# Peripherals.net
KiCad netlist of a schematic drawn in Altium Designer
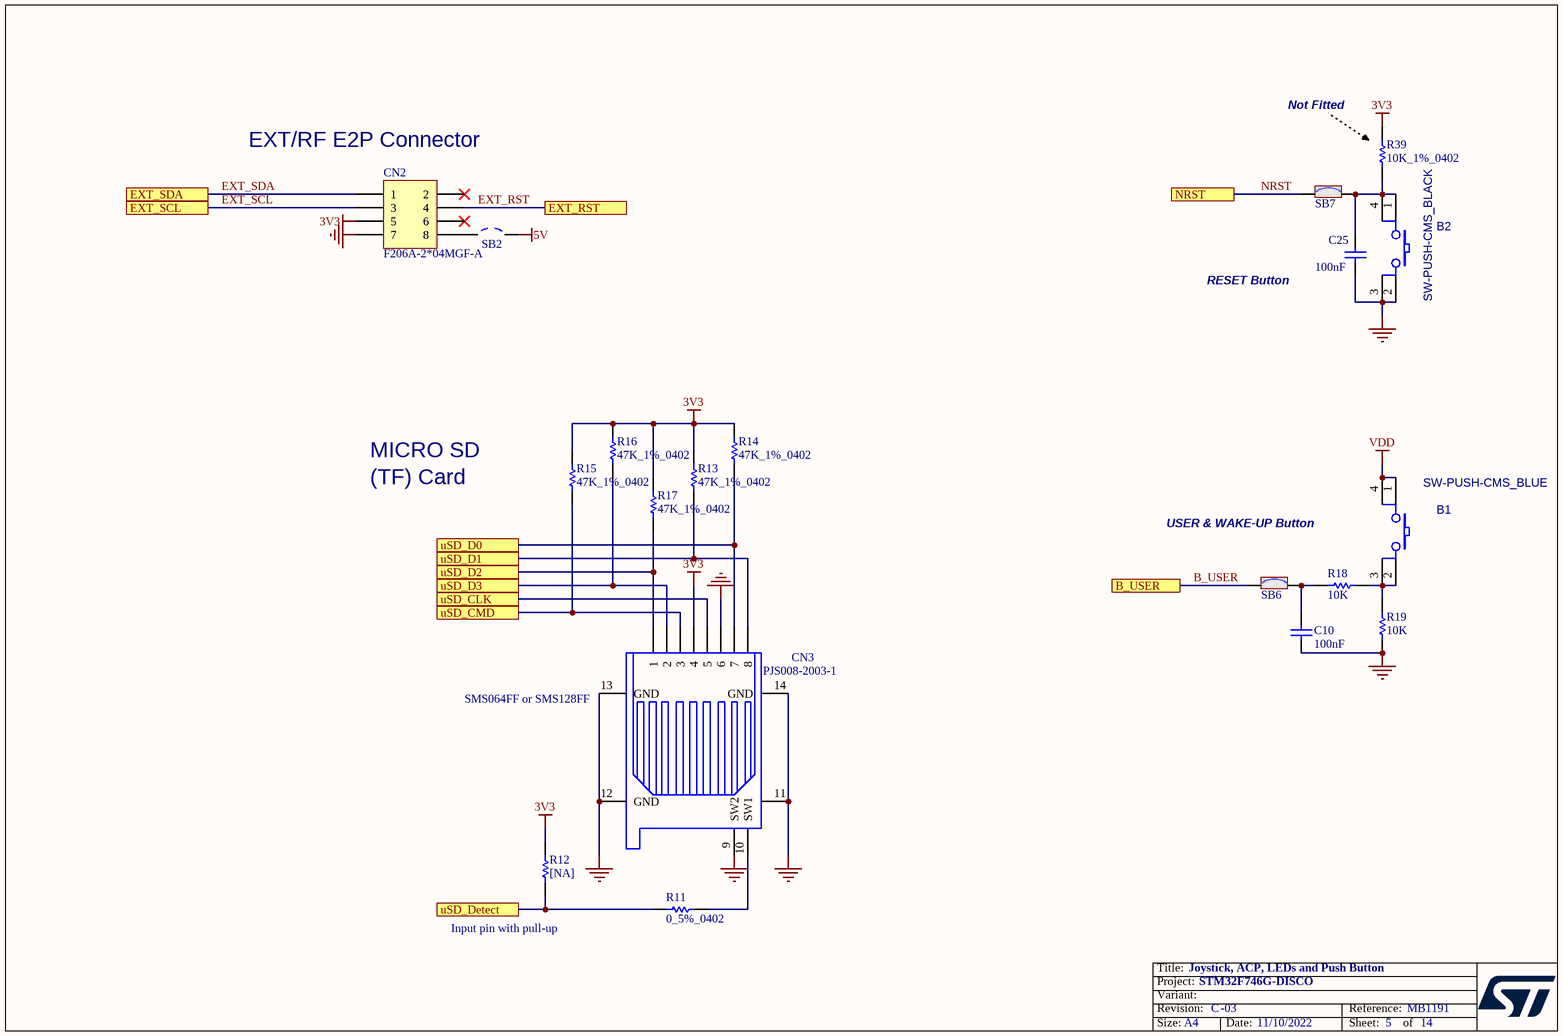
[diagram p0: Peripherals.SchDoc]

(export (version "E")
  (design (tool "Eeschema 10.0.6"))
  (components
    (comp (ref "B1")
      (value "SW-PUSH-CMS_BLUE")
      (footprint "BP1CMS")
      (description "Non-Open Push-Button 0.1A 24V")
      (libsource (lib "MCD_TOOLS") (part "SW-PUSH-CMS_BLUE"))
    )
    (comp (ref "B2")
      (value "SW-PUSH-CMS_BLACK")
      (footprint "BP1CMS")
      (description "Non-Open Push-Button 0.1A 24V")
      (libsource (lib "MCD_TOOLS") (part "SW-PUSH-CMS_BLACK"))
    )
    (comp (ref "C10")
      (value "100nF")
      (footprint "0402C")
      (description "Capacitor,100nF,16V,X7R,10%,0402,YAGEO")
      (libsource (lib "MCD_TOOLS") (part "Cap_100nF_X7R_10%_0402"))
    )
    (comp (ref "C25")
      (value "100nF")
      (footprint "0402C")
      (description "Capacitor,100nF,16V,X7R,10%,0402,YAGEO")
      (libsource (lib "MCD_TOOLS") (part "Cap_100nF_X7R_10%_0402"))
    )
    (comp (ref "CN2")
      (value "F206A-2*04MGF-A")
      (footprint "SSM-104-L-DH")
      (description "Header, 5-Pins, Horizontal Dual row, female SMD")
      (libsource (lib "MCD_TOOLS") (part "F206A-2*04MGF-A"))
    )
    (comp (ref "CN3")
      (value "PJS008-2003-1")
      (footprint "PJS008-2003-1")
      (description "Memory Card Connectors MicroSD Card Conn Revrs Mnt Push-Push")
      (libsource (lib "Mb1191") (part "microSD-PJS008-2003"))
    )
    (comp (ref "R11")
      (value "0_5%_0402")
      (footprint "0402R")
      (description "Resistor,0,0402,5%,YAGEO")
      (libsource (lib "MCD_TOOLS") (part "Res_0_5%_0402"))
    )
    (comp (ref "R12")
      (value "[NA]")
      (footprint "0402R")
      (description "Resistor,[NA],0402")
      (libsource (lib "MCD_TOOLS") (part "Res_NA_0402"))
    )
    (comp (ref "R13")
      (value "47K_1%_0402")
      (footprint "0402R")
      (description "Resistor,47K,0402,1%,YAGEO")
      (libsource (lib "MCD_TOOLS") (part "Res_47K_1%_0402"))
    )
    (comp (ref "R14")
      (value "47K_1%_0402")
      (footprint "0402R")
      (description "Resistor,47K,0402,1%,YAGEO")
      (libsource (lib "MCD_TOOLS") (part "Res_47K_1%_0402"))
    )
    (comp (ref "R15")
      (value "47K_1%_0402")
      (footprint "0402R")
      (description "Resistor,47K,0402,1%,YAGEO")
      (libsource (lib "MCD_TOOLS") (part "Res_47K_1%_0402"))
    )
    (comp (ref "R16")
      (value "47K_1%_0402")
      (footprint "0402R")
      (description "Resistor,47K,0402,1%,YAGEO")
      (libsource (lib "MCD_TOOLS") (part "Res_47K_1%_0402"))
    )
    (comp (ref "R17")
      (value "47K_1%_0402")
      (footprint "0402R")
      (description "Resistor,47K,0402,1%,YAGEO")
      (libsource (lib "MCD_TOOLS") (part "Res_47K_1%_0402"))
    )
    (comp (ref "R18")
      (value "10K")
      (footprint "0402R")
      (description "Resistor,10K,0402,1%,YAGEO")
      (libsource (lib "MCD_TOOLS") (part "Res_10K_1%_0402"))
    )
    (comp (ref "R19")
      (value "10K")
      (footprint "0402R")
      (description "Resistor,10K,0402,1%,YAGEO")
      (libsource (lib "MCD_TOOLS") (part "Res_10K_1%_0402"))
    )
    (comp (ref "R39")
      (value "10K_1%_0402")
      (footprint "0402R")
      (description "Resistor,10K,0402,1%,YAGEO")
      (libsource (lib "MCD_TOOLS") (part "Res_10K_1%_0402"))
    )
    (comp (ref "SB2")
      (value "Solder Bridge OFF")
      (footprint "JP2_SMD")
      (libsource (lib "MCD_TOOLS") (part "SB_OFF"))
    )
    (comp (ref "SB6")
      (value "Solder Bridge ON")
      (footprint "JP2_SMD")
      (libsource (lib "MCD_TOOLS") (part "SB_ON"))
    )
    (comp (ref "SB7")
      (value "Solder Bridge ON")
      (footprint "JP2_SMD")
      (libsource (lib "MCD_TOOLS") (part "SB_ON"))
    )
  )
  (nets
    (net (code "1") (name "/B_USER") (class "Default")
      (node (ref "SB6") (pin "1") (pinfunction "1_1") (pintype "passive"))
    )
    (net (code "2") (name "/EXT_RST") (class "Default")
      (node (ref "CN2") (pin "4") (pinfunction "4_4") (pintype "passive"))
    )
    (net (code "3") (name "/EXT_SCL") (class "Default")
      (node (ref "CN2") (pin "3") (pinfunction "3_3") (pintype "passive"))
    )
    (net (code "4") (name "/EXT_SDA") (class "Default")
      (node (ref "CN2") (pin "1") (pinfunction "1_1") (pintype "passive"))
    )
    (net (code "5") (name "/NRST") (class "Default")
      (node (ref "SB7") (pin "1") (pinfunction "1_1") (pintype "passive"))
    )
    (net (code "6") (name "/uSD_CLK") (class "Default")
      (node (ref "CN3") (pin "5") (pinfunction "5_5") (pintype "passive"))
    )
    (net (code "7") (name "/uSD_CMD") (class "Default")
      (node (ref "CN3") (pin "3") (pinfunction "3_3") (pintype "passive"))
      (node (ref "R15") (pin "1") (pinfunction "1_1") (pintype "passive"))
    )
    (net (code "8") (name "/uSD_D0") (class "Default")
      (node (ref "CN3") (pin "7") (pinfunction "7_7") (pintype "passive"))
      (node (ref "R14") (pin "1") (pinfunction "1_1") (pintype "passive"))
    )
    (net (code "9") (name "/uSD_D1") (class "Default")
      (node (ref "CN3") (pin "8") (pinfunction "8_8") (pintype "passive"))
      (node (ref "R13") (pin "1") (pinfunction "1_1") (pintype "passive"))
    )
    (net (code "10") (name "/uSD_D2") (class "Default")
      (node (ref "CN3") (pin "1") (pinfunction "1_1") (pintype "passive"))
      (node (ref "R17") (pin "1") (pinfunction "1_1") (pintype "passive"))
    )
    (net (code "11") (name "/uSD_D3") (class "Default")
      (node (ref "CN3") (pin "2") (pinfunction "2_2") (pintype "passive"))
      (node (ref "R16") (pin "1") (pinfunction "1_1") (pintype "passive"))
    )
    (net (code "12") (name "/uSD_Detect") (class "Default")
      (node (ref "R11") (pin "1") (pinfunction "1_1") (pintype "passive"))
      (node (ref "R12") (pin "1") (pinfunction "1_1") (pintype "passive"))
    )
    (net (code "13") (name "3V3") (class "Default")
      (node (ref "CN2") (pin "5") (pinfunction "5_5") (pintype "passive"))
      (node (ref "CN3") (pin "4") (pinfunction "4_4") (pintype "passive"))
      (node (ref "R12") (pin "2") (pinfunction "2_2") (pintype "passive"))
      (node (ref "R13") (pin "2") (pinfunction "2_2") (pintype "passive"))
      (node (ref "R14") (pin "2") (pinfunction "2_2") (pintype "passive"))
      (node (ref "R15") (pin "2") (pinfunction "2_2") (pintype "passive"))
      (node (ref "R16") (pin "2") (pinfunction "2_2") (pintype "passive"))
      (node (ref "R17") (pin "2") (pinfunction "2_2") (pintype "passive"))
      (node (ref "R39") (pin "2") (pinfunction "2_2") (pintype "passive"))
    )
    (net (code "14") (name "5V") (class "Default")
      (node (ref "SB2") (pin "2") (pinfunction "2_2") (pintype "passive"))
    )
    (net (code "15") (name "GND") (class "Default")
      (node (ref "B2") (pin "2") (pinfunction "2_2") (pintype "passive"))
      (node (ref "B2") (pin "3") (pinfunction "3_3") (pintype "passive"))
      (node (ref "C10") (pin "1") (pinfunction "1_1") (pintype "passive"))
      (node (ref "C25") (pin "1") (pinfunction "1_1") (pintype "passive"))
      (node (ref "CN2") (pin "7") (pinfunction "7_7") (pintype "passive"))
      (node (ref "CN3") (pin "11") (pinfunction "GND_11") (pintype "passive"))
      (node (ref "CN3") (pin "12") (pinfunction "GND_12") (pintype "passive"))
      (node (ref "CN3") (pin "13") (pinfunction "GND_13") (pintype "passive"))
      (node (ref "CN3") (pin "14") (pinfunction "GND_14") (pintype "passive"))
      (node (ref "CN3") (pin "6") (pinfunction "6_6") (pintype "passive"))
      (node (ref "CN3") (pin "9") (pinfunction "SW2_9") (pintype "passive"))
      (node (ref "R19") (pin "1") (pinfunction "1_1") (pintype "passive"))
    )
    (net (code "16") (name "Net-(B1-Pad2)") (class "Default")
      (node (ref "B1") (pin "2") (pinfunction "2_2") (pintype "passive"))
      (node (ref "B1") (pin "3") (pinfunction "3_3") (pintype "passive"))
      (node (ref "R18") (pin "2") (pinfunction "2_2") (pintype "passive"))
      (node (ref "R19") (pin "2") (pinfunction "2_2") (pintype "passive"))
    )
    (net (code "17") (name "Net-(B2-Pad1)") (class "Default")
      (node (ref "B2") (pin "1") (pinfunction "1_1") (pintype "passive"))
      (node (ref "B2") (pin "4") (pinfunction "4_4") (pintype "passive"))
      (node (ref "C25") (pin "2") (pinfunction "2_2") (pintype "passive"))
      (node (ref "R39") (pin "1") (pinfunction "1_1") (pintype "passive"))
      (node (ref "SB7") (pin "2") (pinfunction "2_2") (pintype "passive"))
    )
    (net (code "18") (name "Net-(C10-Pad2)") (class "Default")
      (node (ref "C10") (pin "2") (pinfunction "2_2") (pintype "passive"))
      (node (ref "R18") (pin "1") (pinfunction "1_1") (pintype "passive"))
      (node (ref "SB6") (pin "2") (pinfunction "2_2") (pintype "passive"))
    )
    (net (code "19") (name "Net-(CN2-Pad8)") (class "Default")
      (node (ref "CN2") (pin "8") (pinfunction "8_8") (pintype "passive"))
      (node (ref "SB2") (pin "1") (pinfunction "1_1") (pintype "passive"))
    )
    (net (code "20") (name "Net-(CN3-SW1)") (class "Default")
      (node (ref "CN3") (pin "10") (pinfunction "SW1_10") (pintype "passive"))
      (node (ref "R11") (pin "2") (pinfunction "2_2") (pintype "passive"))
    )
    (net (code "21") (name "VDD") (class "Default")
      (node (ref "B1") (pin "1") (pinfunction "1_1") (pintype "passive"))
      (node (ref "B1") (pin "4") (pinfunction "4_4") (pintype "passive"))
    )
    (net (code "22") (name "unconnected-(CN2-Pad2)") (class "Default")
      (node (ref "CN2") (pin "2") (pinfunction "2_2") (pintype "passive+no_connect"))
    )
    (net (code "23") (name "unconnected-(CN2-Pad6)") (class "Default")
      (node (ref "CN2") (pin "6") (pinfunction "6_6") (pintype "passive+no_connect"))
    )
  )
)
